# irobot_virtualwall.net
KiCad netlist of a schematic drawn in EAGLE
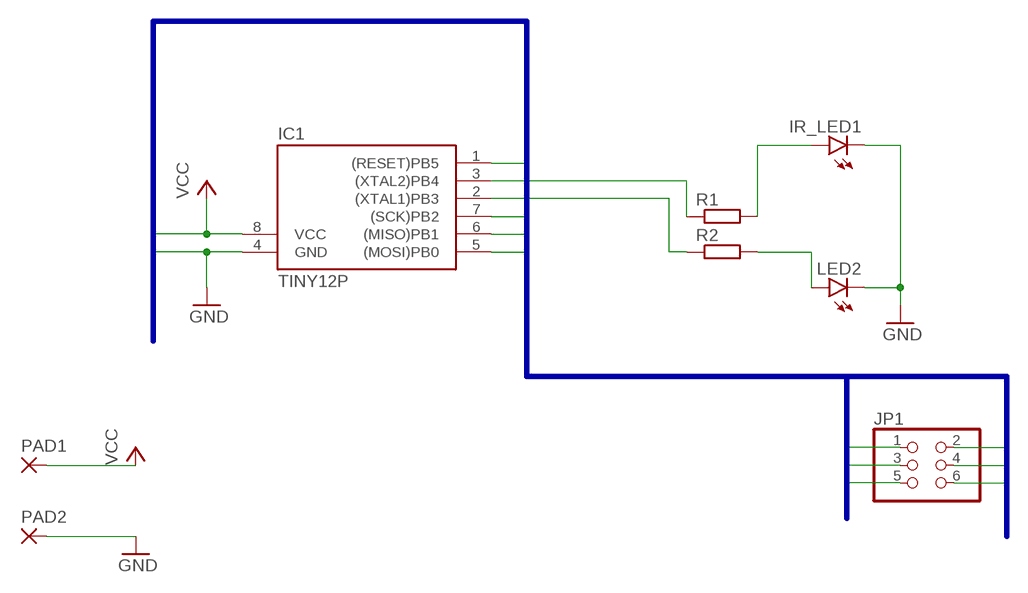
[diagram p0: schematic, sheet 1]

(export (version "E")
  (design (tool "Eeschema 10.0.6"))
  (components
    (comp (ref "IC1")
      (value "TINY12P")
      (footprint "eagle-import:DIL08")
      (libsource (lib "eagle-import") (part "TINY12P"))
    )
    (comp (ref "IR_LED1")
      (value "LED5MM")
      (footprint "eagle-import:LED5MM")
      (libsource (lib "eagle-import") (part "LED5MM"))
    )
    (comp (ref "JP1")
      (value "PINHD-2X3")
      (footprint "eagle-import:2X03")
      (libsource (lib "eagle-import") (part "PINHD-2X3"))
    )
    (comp (ref "LED2")
      (value "LED5MM")
      (footprint "eagle-import:LED5MM")
      (libsource (lib "eagle-import") (part "LED5MM"))
    )
    (comp (ref "PAD1")
      (value "2,54/0,8")
      (footprint "eagle-import:2,54_0,8")
      (libsource (lib "eagle-import") (part "2,54/0,8"))
    )
    (comp (ref "PAD2")
      (value "2,54/0,8")
      (footprint "eagle-import:2,54_0,8")
      (libsource (lib "eagle-import") (part "2,54/0,8"))
    )
    (comp (ref "R1")
      (value "R-EU_0207/10")
      (footprint "eagle-import:0207_10")
      (libsource (lib "eagle-import") (part "R-EU_0207/10"))
    )
    (comp (ref "R2")
      (value "R-EU_0207/10")
      (footprint "eagle-import:0207_10")
      (libsource (lib "eagle-import") (part "R-EU_0207/10"))
    )
  )
  (nets
    (net (code "1") (name "/CLK") (class "Default")
      (node (ref "IC1") (pin "7") (pinfunction "(SCK)PB2_7") (pintype "bidirectional"))
      (node (ref "JP1") (pin "3") (pinfunction "3_3") (pintype "passive"))
    )
    (net (code "2") (name "/MISO") (class "Default")
      (node (ref "IC1") (pin "6") (pinfunction "(MISO)PB1_6") (pintype "bidirectional"))
      (node (ref "JP1") (pin "1") (pinfunction "1_1") (pintype "passive"))
    )
    (net (code "3") (name "/MOSI") (class "Default")
      (node (ref "IC1") (pin "5") (pinfunction "(MOSI)PB0_5") (pintype "bidirectional"))
      (node (ref "JP1") (pin "4") (pinfunction "4_4") (pintype "passive"))
    )
    (net (code "4") (name "/RST") (class "Default")
      (node (ref "IC1") (pin "1") (pinfunction "(RESET)PB5_1") (pintype "bidirectional"))
      (node (ref "JP1") (pin "5") (pinfunction "5_5") (pintype "passive"))
    )
    (net (code "5") (name "GND") (class "Default")
      (node (ref "IC1") (pin "4") (pinfunction "GND_4") (pintype "power_in"))
      (node (ref "IR_LED1") (pin "K") (pinfunction "C_K") (pintype "passive"))
      (node (ref "JP1") (pin "6") (pinfunction "6_6") (pintype "passive"))
      (node (ref "LED2") (pin "K") (pinfunction "C_K") (pintype "passive"))
      (node (ref "PAD2") (pin "1") (pinfunction "P_1") (pintype "passive"))
    )
    (net (code "6") (name "Net-(IC1-(XTAL1)PB3)") (class "Default")
      (node (ref "IC1") (pin "2") (pinfunction "(XTAL1)PB3_2") (pintype "bidirectional"))
      (node (ref "R2") (pin "1") (pinfunction "1_1") (pintype "passive"))
    )
    (net (code "7") (name "Net-(IC1-(XTAL2)PB4)") (class "Default")
      (node (ref "IC1") (pin "3") (pinfunction "(XTAL2)PB4_3") (pintype "bidirectional"))
      (node (ref "R1") (pin "1") (pinfunction "1_1") (pintype "passive"))
    )
    (net (code "8") (name "Net-(IR_LED1-PadA)") (class "Default")
      (node (ref "IR_LED1") (pin "A") (pinfunction "A_A") (pintype "passive"))
      (node (ref "R1") (pin "2") (pinfunction "2_2") (pintype "passive"))
    )
    (net (code "9") (name "Net-(LED2-PadA)") (class "Default")
      (node (ref "LED2") (pin "A") (pinfunction "A_A") (pintype "passive"))
      (node (ref "R2") (pin "2") (pinfunction "2_2") (pintype "passive"))
    )
    (net (code "10") (name "VCC") (class "Default")
      (node (ref "IC1") (pin "8") (pinfunction "VCC_8") (pintype "power_in"))
      (node (ref "JP1") (pin "2") (pinfunction "2_2") (pintype "passive"))
      (node (ref "PAD1") (pin "1") (pinfunction "P_1") (pintype "passive"))
    )
  )
)
